# 128A_Breakout_V1_1.net
KiCad netlist of a schematic drawn in EAGLE
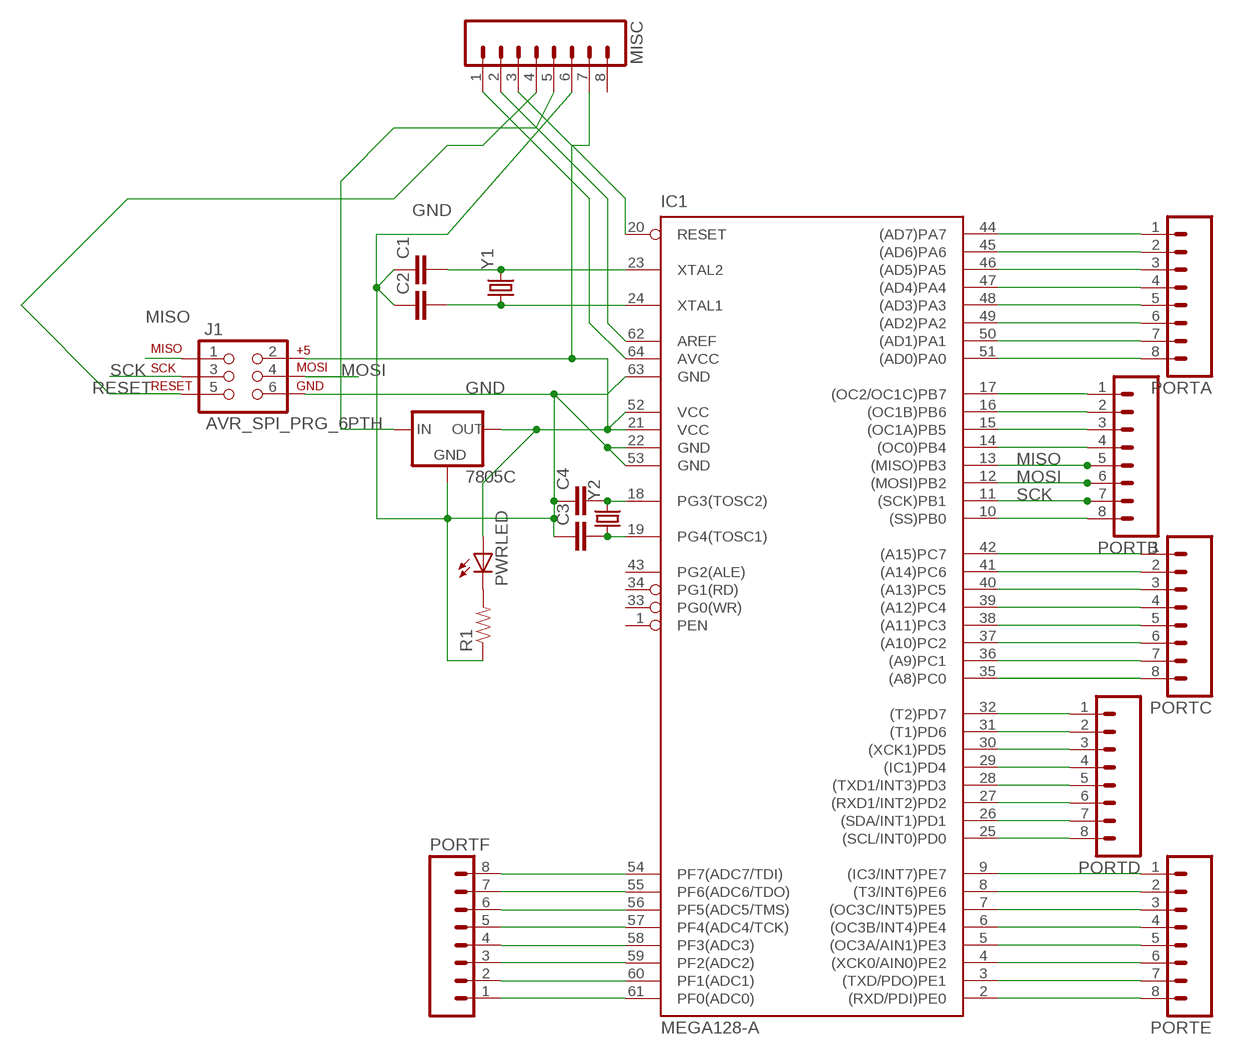
[diagram p0: schematic, sheet 1]

(export (version "E")
  (design (tool "Eeschema 10.0.6"))
  (components
    (comp (ref "7805C")
      (value "V_REG_78XXSIDE")
      (footprint "eagle-import:78XXL")
      (libsource (lib "eagle-import") (part "V_REG_78XXSIDE"))
    )
    (comp (ref "C1")
      (value "CAP1206")
      (footprint "eagle-import:1206")
      (libsource (lib "eagle-import") (part "CAP1206"))
    )
    (comp (ref "C2")
      (value "CAP1206")
      (footprint "eagle-import:1206")
      (libsource (lib "eagle-import") (part "CAP1206"))
    )
    (comp (ref "C3")
      (value "CAP1206")
      (footprint "eagle-import:1206")
      (libsource (lib "eagle-import") (part "CAP1206"))
    )
    (comp (ref "C4")
      (value "CAP1206")
      (footprint "eagle-import:1206")
      (libsource (lib "eagle-import") (part "CAP1206"))
    )
    (comp (ref "IC1")
      (value "MEGA128-A")
      (footprint "eagle-import:TQFP64")
      (fields (field (name "MPN") "ATMEGA128-16AU"))
      (libsource (lib "eagle-import") (part "MEGA128-A"))
    )
    (comp (ref "J1")
      (value "AVR_SPI_PRG_6PTH")
      (footprint "eagle-import:2X3")
      (libsource (lib "eagle-import") (part "AVR_SPI_PRG_6PTH"))
    )
    (comp (ref "MISC")
      (value "M081X08")
      (footprint "eagle-import:1X08")
      (libsource (lib "eagle-import") (part "M081X08"))
    )
    (comp (ref "PORTA")
      (value "M081X08")
      (footprint "eagle-import:1X08")
      (libsource (lib "eagle-import") (part "M081X08"))
    )
    (comp (ref "PORTB")
      (value "M081X08")
      (footprint "eagle-import:1X08")
      (libsource (lib "eagle-import") (part "M081X08"))
    )
    (comp (ref "PORTC")
      (value "M081X08")
      (footprint "eagle-import:1X08")
      (libsource (lib "eagle-import") (part "M081X08"))
    )
    (comp (ref "PORTD")
      (value "M081X08")
      (footprint "eagle-import:1X08")
      (libsource (lib "eagle-import") (part "M081X08"))
    )
    (comp (ref "PORTE")
      (value "M081X08")
      (footprint "eagle-import:1X08")
      (libsource (lib "eagle-import") (part "M081X08"))
    )
    (comp (ref "PORTF")
      (value "M081X08")
      (footprint "eagle-import:1X08")
      (libsource (lib "eagle-import") (part "M081X08"))
    )
    (comp (ref "PWRLED")
      (value "LED-FKIT-1206")
      (footprint "eagle-import:FKIT-LED-1206")
      (libsource (lib "eagle-import") (part "LED-FKIT-1206"))
    )
    (comp (ref "R1")
      (value "RESISTOR1206")
      (footprint "eagle-import:1206")
      (libsource (lib "eagle-import") (part "RESISTOR1206"))
    )
    (comp (ref "Y1")
      (value "CRYSTALHC49US")
      (footprint "eagle-import:HC49US")
      (libsource (lib "eagle-import") (part "CRYSTALHC49US"))
    )
    (comp (ref "Y2")
      (value "CRYSTALTC26H_EZ")
      (footprint "eagle-import:TC26HEZ")
      (libsource (lib "eagle-import") (part "CRYSTALTC26H_EZ"))
    )
  )
  (nets
    (net (code "1") (name "/GND") (class "Default")
      (node (ref "7805C") (pin "GND") (pinfunction "GND_GND") (pintype "input"))
      (node (ref "C1") (pin "1") (pinfunction "1_1") (pintype "passive"))
      (node (ref "C2") (pin "1") (pinfunction "1_1") (pintype "passive"))
      (node (ref "C3") (pin "1") (pinfunction "1_1") (pintype "passive"))
      (node (ref "C4") (pin "1") (pinfunction "1_1") (pintype "passive"))
      (node (ref "IC1") (pin "22") (pinfunction "GND_22") (pintype "power_in"))
      (node (ref "IC1") (pin "53") (pinfunction "GND_53") (pintype "power_in"))
      (node (ref "IC1") (pin "63") (pinfunction "GND_63") (pintype "power_in"))
      (node (ref "J1") (pin "6") (pinfunction "6_6") (pintype "passive"))
      (node (ref "MISC") (pin "6") (pinfunction "6_6") (pintype "passive"))
      (node (ref "R1") (pin "1") (pinfunction "1_1") (pintype "passive"))
    )
    (net (code "2") (name "/MISO") (class "Default")
      (node (ref "IC1") (pin "13") (pinfunction "(MISO)PB3_13") (pintype "bidirectional"))
      (node (ref "J1") (pin "1") (pinfunction "1_1") (pintype "passive"))
      (node (ref "PORTB") (pin "5") (pinfunction "5_5") (pintype "passive"))
    )
    (net (code "3") (name "/MOSI") (class "Default")
      (node (ref "IC1") (pin "12") (pinfunction "(MOSI)PB2_12") (pintype "bidirectional"))
      (node (ref "J1") (pin "4") (pinfunction "4_4") (pintype "passive"))
      (node (ref "PORTB") (pin "6") (pinfunction "6_6") (pintype "passive"))
    )
    (net (code "4") (name "/RESET") (class "Default")
      (node (ref "J1") (pin "5") (pinfunction "5_5") (pintype "passive"))
      (node (ref "MISC") (pin "4") (pinfunction "4_4") (pintype "passive"))
    )
    (net (code "5") (name "/SCK") (class "Default")
      (node (ref "IC1") (pin "11") (pinfunction "(SCK)PB1_11") (pintype "bidirectional"))
      (node (ref "J1") (pin "3") (pinfunction "3_3") (pintype "passive"))
      (node (ref "PORTB") (pin "7") (pinfunction "7_7") (pintype "passive"))
    )
    (net (code "6") (name "Net-(7805C-PadIN)") (class "Default")
      (node (ref "7805C") (pin "IN") (pinfunction "IN_IN") (pintype "input"))
      (node (ref "MISC") (pin "5") (pinfunction "5_5") (pintype "passive"))
    )
    (net (code "7") (name "Net-(7805C-PadOUT)") (class "Default")
      (node (ref "7805C") (pin "OUT") (pinfunction "OUT_OUT") (pintype "output"))
      (node (ref "IC1") (pin "21") (pinfunction "VCC_21") (pintype "power_in"))
      (node (ref "IC1") (pin "52") (pinfunction "VCC_52") (pintype "power_in"))
      (node (ref "J1") (pin "2") (pinfunction "2_2") (pintype "passive"))
      (node (ref "MISC") (pin "7") (pinfunction "7_7") (pintype "passive"))
      (node (ref "PWRLED") (pin "A") (pinfunction "A_A") (pintype "passive"))
    )
    (net (code "8") (name "Net-(IC1-(A8)PC0)") (class "Default")
      (node (ref "IC1") (pin "35") (pinfunction "(A8)PC0_35") (pintype "output"))
      (node (ref "PORTC") (pin "8") (pinfunction "8_8") (pintype "passive"))
    )
    (net (code "9") (name "Net-(IC1-(A9)PC1)") (class "Default")
      (node (ref "IC1") (pin "36") (pinfunction "(A9)PC1_36") (pintype "output"))
      (node (ref "PORTC") (pin "7") (pinfunction "7_7") (pintype "passive"))
    )
    (net (code "10") (name "Net-(IC1-(A10)PC2)") (class "Default")
      (node (ref "IC1") (pin "37") (pinfunction "(A10)PC2_37") (pintype "output"))
      (node (ref "PORTC") (pin "6") (pinfunction "6_6") (pintype "passive"))
    )
    (net (code "11") (name "Net-(IC1-(A11)PC3)") (class "Default")
      (node (ref "IC1") (pin "38") (pinfunction "(A11)PC3_38") (pintype "output"))
      (node (ref "PORTC") (pin "5") (pinfunction "5_5") (pintype "passive"))
    )
    (net (code "12") (name "Net-(IC1-(A12)PC4)") (class "Default")
      (node (ref "IC1") (pin "39") (pinfunction "(A12)PC4_39") (pintype "output"))
      (node (ref "PORTC") (pin "4") (pinfunction "4_4") (pintype "passive"))
    )
    (net (code "13") (name "Net-(IC1-(A13)PC5)") (class "Default")
      (node (ref "IC1") (pin "40") (pinfunction "(A13)PC5_40") (pintype "output"))
      (node (ref "PORTC") (pin "3") (pinfunction "3_3") (pintype "passive"))
    )
    (net (code "14") (name "Net-(IC1-(A14)PC6)") (class "Default")
      (node (ref "IC1") (pin "41") (pinfunction "(A14)PC6_41") (pintype "output"))
      (node (ref "PORTC") (pin "2") (pinfunction "2_2") (pintype "passive"))
    )
    (net (code "15") (name "Net-(IC1-(A15)PC7)") (class "Default")
      (node (ref "IC1") (pin "42") (pinfunction "(A15)PC7_42") (pintype "output"))
      (node (ref "PORTC") (pin "1") (pinfunction "1_1") (pintype "passive"))
    )
    (net (code "16") (name "Net-(IC1-(AD0)PA0)") (class "Default")
      (node (ref "IC1") (pin "51") (pinfunction "(AD0)PA0_51") (pintype "bidirectional"))
      (node (ref "PORTA") (pin "8") (pinfunction "8_8") (pintype "passive"))
    )
    (net (code "17") (name "Net-(IC1-(AD1)PA1)") (class "Default")
      (node (ref "IC1") (pin "50") (pinfunction "(AD1)PA1_50") (pintype "bidirectional"))
      (node (ref "PORTA") (pin "7") (pinfunction "7_7") (pintype "passive"))
    )
    (net (code "18") (name "Net-(IC1-(AD2)PA2)") (class "Default")
      (node (ref "IC1") (pin "49") (pinfunction "(AD2)PA2_49") (pintype "bidirectional"))
      (node (ref "PORTA") (pin "6") (pinfunction "6_6") (pintype "passive"))
    )
    (net (code "19") (name "Net-(IC1-(AD3)PA3)") (class "Default")
      (node (ref "IC1") (pin "48") (pinfunction "(AD3)PA3_48") (pintype "bidirectional"))
      (node (ref "PORTA") (pin "5") (pinfunction "5_5") (pintype "passive"))
    )
    (net (code "20") (name "Net-(IC1-(AD4)PA4)") (class "Default")
      (node (ref "IC1") (pin "47") (pinfunction "(AD4)PA4_47") (pintype "bidirectional"))
      (node (ref "PORTA") (pin "4") (pinfunction "4_4") (pintype "passive"))
    )
    (net (code "21") (name "Net-(IC1-(AD5)PA5)") (class "Default")
      (node (ref "IC1") (pin "46") (pinfunction "(AD5)PA5_46") (pintype "bidirectional"))
      (node (ref "PORTA") (pin "3") (pinfunction "3_3") (pintype "passive"))
    )
    (net (code "22") (name "Net-(IC1-(AD6)PA6)") (class "Default")
      (node (ref "IC1") (pin "45") (pinfunction "(AD6)PA6_45") (pintype "bidirectional"))
      (node (ref "PORTA") (pin "2") (pinfunction "2_2") (pintype "passive"))
    )
    (net (code "23") (name "Net-(IC1-(AD7)PA7)") (class "Default")
      (node (ref "IC1") (pin "44") (pinfunction "(AD7)PA7_44") (pintype "bidirectional"))
      (node (ref "PORTA") (pin "1") (pinfunction "1_1") (pintype "passive"))
    )
    (net (code "24") (name "Net-(IC1-(IC1)PD4)") (class "Default")
      (node (ref "IC1") (pin "29") (pinfunction "(IC1)PD4_29") (pintype "bidirectional"))
      (node (ref "PORTD") (pin "4") (pinfunction "4_4") (pintype "passive"))
    )
    (net (code "25") (name "Net-(IC1-(IC3{slash}INT7)PE7)") (class "Default")
      (node (ref "IC1") (pin "9") (pinfunction "(IC3/INT7)PE7_9") (pintype "bidirectional"))
      (node (ref "PORTE") (pin "1") (pinfunction "1_1") (pintype "passive"))
    )
    (net (code "26") (name "Net-(IC1-(OC0)PB4)") (class "Default")
      (node (ref "IC1") (pin "14") (pinfunction "(OC0)PB4_14") (pintype "bidirectional"))
      (node (ref "PORTB") (pin "4") (pinfunction "4_4") (pintype "passive"))
    )
    (net (code "27") (name "Net-(IC1-(OC1A)PB5)") (class "Default")
      (node (ref "IC1") (pin "15") (pinfunction "(OC1A)PB5_15") (pintype "bidirectional"))
      (node (ref "PORTB") (pin "3") (pinfunction "3_3") (pintype "passive"))
    )
    (net (code "28") (name "Net-(IC1-(OC1B)PB6)") (class "Default")
      (node (ref "IC1") (pin "16") (pinfunction "(OC1B)PB6_16") (pintype "bidirectional"))
      (node (ref "PORTB") (pin "2") (pinfunction "2_2") (pintype "passive"))
    )
    (net (code "29") (name "Net-(IC1-(OC2{slash}OC1C)PB7)") (class "Default")
      (node (ref "IC1") (pin "17") (pinfunction "(OC2/OC1C)PB7_17") (pintype "bidirectional"))
      (node (ref "PORTB") (pin "1") (pinfunction "1_1") (pintype "passive"))
    )
    (net (code "30") (name "Net-(IC1-(OC3A{slash}AIN1)PE3)") (class "Default")
      (node (ref "IC1") (pin "5") (pinfunction "(OC3A/AIN1)PE3_5") (pintype "bidirectional"))
      (node (ref "PORTE") (pin "5") (pinfunction "5_5") (pintype "passive"))
    )
    (net (code "31") (name "Net-(IC1-(OC3B{slash}INT4)PE4)") (class "Default")
      (node (ref "IC1") (pin "6") (pinfunction "(OC3B/INT4)PE4_6") (pintype "bidirectional"))
      (node (ref "PORTE") (pin "4") (pinfunction "4_4") (pintype "passive"))
    )
    (net (code "32") (name "Net-(IC1-(OC3C{slash}INT5)PE5)") (class "Default")
      (node (ref "IC1") (pin "7") (pinfunction "(OC3C/INT5)PE5_7") (pintype "bidirectional"))
      (node (ref "PORTE") (pin "3") (pinfunction "3_3") (pintype "passive"))
    )
    (net (code "33") (name "Net-(IC1-(RXD1{slash}INT2)PD2)") (class "Default")
      (node (ref "IC1") (pin "27") (pinfunction "(RXD1/INT2)PD2_27") (pintype "bidirectional"))
      (node (ref "PORTD") (pin "6") (pinfunction "6_6") (pintype "passive"))
    )
    (net (code "34") (name "Net-(IC1-(RXD{slash}PDI)PE0)") (class "Default")
      (node (ref "IC1") (pin "2") (pinfunction "(RXD/PDI)PE0_2") (pintype "bidirectional"))
      (node (ref "PORTE") (pin "8") (pinfunction "8_8") (pintype "passive"))
    )
    (net (code "35") (name "Net-(IC1-(SCL{slash}INT0)PD0)") (class "Default")
      (node (ref "IC1") (pin "25") (pinfunction "(SCL/INT0)PD0_25") (pintype "bidirectional"))
      (node (ref "PORTD") (pin "8") (pinfunction "8_8") (pintype "passive"))
    )
    (net (code "36") (name "Net-(IC1-(SDA{slash}INT1)PD1)") (class "Default")
      (node (ref "IC1") (pin "26") (pinfunction "(SDA/INT1)PD1_26") (pintype "bidirectional"))
      (node (ref "PORTD") (pin "7") (pinfunction "7_7") (pintype "passive"))
    )
    (net (code "37") (name "Net-(IC1-(SS)PB0)") (class "Default")
      (node (ref "IC1") (pin "10") (pinfunction "(SS)PB0_10") (pintype "bidirectional"))
      (node (ref "PORTB") (pin "8") (pinfunction "8_8") (pintype "passive"))
    )
    (net (code "38") (name "Net-(IC1-(T1)PD6)") (class "Default")
      (node (ref "IC1") (pin "31") (pinfunction "(T1)PD6_31") (pintype "bidirectional"))
      (node (ref "PORTD") (pin "2") (pinfunction "2_2") (pintype "passive"))
    )
    (net (code "39") (name "Net-(IC1-(T2)PD7)") (class "Default")
      (node (ref "IC1") (pin "32") (pinfunction "(T2)PD7_32") (pintype "bidirectional"))
      (node (ref "PORTD") (pin "1") (pinfunction "1_1") (pintype "passive"))
    )
    (net (code "40") (name "Net-(IC1-(T3{slash}INT6)PE6)") (class "Default")
      (node (ref "IC1") (pin "8") (pinfunction "(T3/INT6)PE6_8") (pintype "bidirectional"))
      (node (ref "PORTE") (pin "2") (pinfunction "2_2") (pintype "passive"))
    )
    (net (code "41") (name "Net-(IC1-(TXD1{slash}INT3)PD3)") (class "Default")
      (node (ref "IC1") (pin "28") (pinfunction "(TXD1/INT3)PD3_28") (pintype "bidirectional"))
      (node (ref "PORTD") (pin "5") (pinfunction "5_5") (pintype "passive"))
    )
    (net (code "42") (name "Net-(IC1-(TXD{slash}PDO)PE1)") (class "Default")
      (node (ref "IC1") (pin "3") (pinfunction "(TXD/PDO)PE1_3") (pintype "bidirectional"))
      (node (ref "PORTE") (pin "7") (pinfunction "7_7") (pintype "passive"))
    )
    (net (code "43") (name "Net-(IC1-(XCK0{slash}AIN0)PE2)") (class "Default")
      (node (ref "IC1") (pin "4") (pinfunction "(XCK0/AIN0)PE2_4") (pintype "bidirectional"))
      (node (ref "PORTE") (pin "6") (pinfunction "6_6") (pintype "passive"))
    )
    (net (code "44") (name "Net-(IC1-(XCK1)PD5)") (class "Default")
      (node (ref "IC1") (pin "30") (pinfunction "(XCK1)PD5_30") (pintype "bidirectional"))
      (node (ref "PORTD") (pin "3") (pinfunction "3_3") (pintype "passive"))
    )
    (net (code "45") (name "Net-(IC1-AREF)") (class "Default")
      (node (ref "IC1") (pin "62") (pinfunction "AREF_62") (pintype "passive"))
      (node (ref "MISC") (pin "2") (pinfunction "2_2") (pintype "passive"))
    )
    (net (code "46") (name "Net-(IC1-AVCC)") (class "Default")
      (node (ref "IC1") (pin "64") (pinfunction "AVCC_64") (pintype "power_in"))
      (node (ref "MISC") (pin "1") (pinfunction "1_1") (pintype "passive"))
    )
    (net (code "47") (name "Net-(IC1-PF0(ADC0))") (class "Default")
      (node (ref "IC1") (pin "61") (pinfunction "PF0(ADC0)_61") (pintype "input"))
      (node (ref "PORTF") (pin "1") (pinfunction "1_1") (pintype "passive"))
    )
    (net (code "48") (name "Net-(IC1-PF1(ADC1))") (class "Default")
      (node (ref "IC1") (pin "60") (pinfunction "PF1(ADC1)_60") (pintype "input"))
      (node (ref "PORTF") (pin "2") (pinfunction "2_2") (pintype "passive"))
    )
    (net (code "49") (name "Net-(IC1-PF2(ADC2))") (class "Default")
      (node (ref "IC1") (pin "59") (pinfunction "PF2(ADC2)_59") (pintype "input"))
      (node (ref "PORTF") (pin "3") (pinfunction "3_3") (pintype "passive"))
    )
    (net (code "50") (name "Net-(IC1-PF3(ADC3))") (class "Default")
      (node (ref "IC1") (pin "58") (pinfunction "PF3(ADC3)_58") (pintype "input"))
      (node (ref "PORTF") (pin "4") (pinfunction "4_4") (pintype "passive"))
    )
    (net (code "51") (name "Net-(IC1-PF4(ADC4{slash}TCK))") (class "Default")
      (node (ref "IC1") (pin "57") (pinfunction "PF4(ADC4/TCK)_57") (pintype "input"))
      (node (ref "PORTF") (pin "5") (pinfunction "5_5") (pintype "passive"))
    )
    (net (code "52") (name "Net-(IC1-PF5(ADC5{slash}TMS))") (class "Default")
      (node (ref "IC1") (pin "56") (pinfunction "PF5(ADC5/TMS)_56") (pintype "input"))
      (node (ref "PORTF") (pin "6") (pinfunction "6_6") (pintype "passive"))
    )
    (net (code "53") (name "Net-(IC1-PF6(ADC6{slash}TDO))") (class "Default")
      (node (ref "IC1") (pin "55") (pinfunction "PF6(ADC6/TDO)_55") (pintype "input"))
      (node (ref "PORTF") (pin "7") (pinfunction "7_7") (pintype "passive"))
    )
    (net (code "54") (name "Net-(IC1-PF7(ADC7{slash}TDI))") (class "Default")
      (node (ref "IC1") (pin "54") (pinfunction "PF7(ADC7/TDI)_54") (pintype "input"))
      (node (ref "PORTF") (pin "8") (pinfunction "8_8") (pintype "passive"))
    )
    (net (code "55") (name "Net-(IC1-PG3(TOSC2))") (class "Default")
      (node (ref "C4") (pin "2") (pinfunction "2_2") (pintype "passive"))
      (node (ref "IC1") (pin "18") (pinfunction "PG3(TOSC2)_18") (pintype "bidirectional"))
      (node (ref "Y2") (pin "2") (pinfunction "2_2") (pintype "passive"))
    )
    (net (code "56") (name "Net-(IC1-PG4(TOSC1))") (class "Default")
      (node (ref "C3") (pin "2") (pinfunction "2_2") (pintype "passive"))
      (node (ref "IC1") (pin "19") (pinfunction "PG4(TOSC1)_19") (pintype "bidirectional"))
      (node (ref "Y2") (pin "1") (pinfunction "1_1") (pintype "passive"))
    )
    (net (code "57") (name "Net-(IC1-RESET)") (class "Default")
      (node (ref "IC1") (pin "20") (pinfunction "RESET_20") (pintype "input"))
      (node (ref "MISC") (pin "3") (pinfunction "3_3") (pintype "passive"))
    )
    (net (code "58") (name "Net-(IC1-XTAL1)") (class "Default")
      (node (ref "C2") (pin "2") (pinfunction "2_2") (pintype "passive"))
      (node (ref "IC1") (pin "24") (pinfunction "XTAL1_24") (pintype "bidirectional"))
      (node (ref "Y1") (pin "1") (pinfunction "1_1") (pintype "passive"))
    )
    (net (code "59") (name "Net-(IC1-XTAL2)") (class "Default")
      (node (ref "C1") (pin "2") (pinfunction "2_2") (pintype "passive"))
      (node (ref "IC1") (pin "23") (pinfunction "XTAL2_23") (pintype "bidirectional"))
      (node (ref "Y1") (pin "2") (pinfunction "2_2") (pintype "passive"))
    )
    (net (code "60") (name "Net-(PWRLED-PadC)") (class "Default")
      (node (ref "PWRLED") (pin "C") (pinfunction "C_C") (pintype "passive"))
      (node (ref "R1") (pin "2") (pinfunction "2_2") (pintype "passive"))
    )
    (net (code "61") (name "unconnected-(IC1-PEN-Pad1)") (class "Default")
      (node (ref "IC1") (pin "1") (pinfunction "PEN_1") (pintype "input"))
    )
    (net (code "62") (name "unconnected-(IC1-PG0(WR)-Pad33)") (class "Default")
      (node (ref "IC1") (pin "33") (pinfunction "PG0(WR)_33") (pintype "bidirectional"))
    )
    (net (code "63") (name "unconnected-(IC1-PG1(RD)-Pad34)") (class "Default")
      (node (ref "IC1") (pin "34") (pinfunction "PG1(RD)_34") (pintype "bidirectional"))
    )
    (net (code "64") (name "unconnected-(IC1-PG2(ALE)-Pad43)") (class "Default")
      (node (ref "IC1") (pin "43") (pinfunction "PG2(ALE)_43") (pintype "bidirectional"))
    )
    (net (code "65") (name "unconnected-(MISC-Pad8)") (class "Default")
      (node (ref "MISC") (pin "8") (pinfunction "8_8") (pintype "passive"))
    )
  )
)
